# MC_Isolation_Schematic.net
KiCad netlist of a schematic drawn in Altium Designer
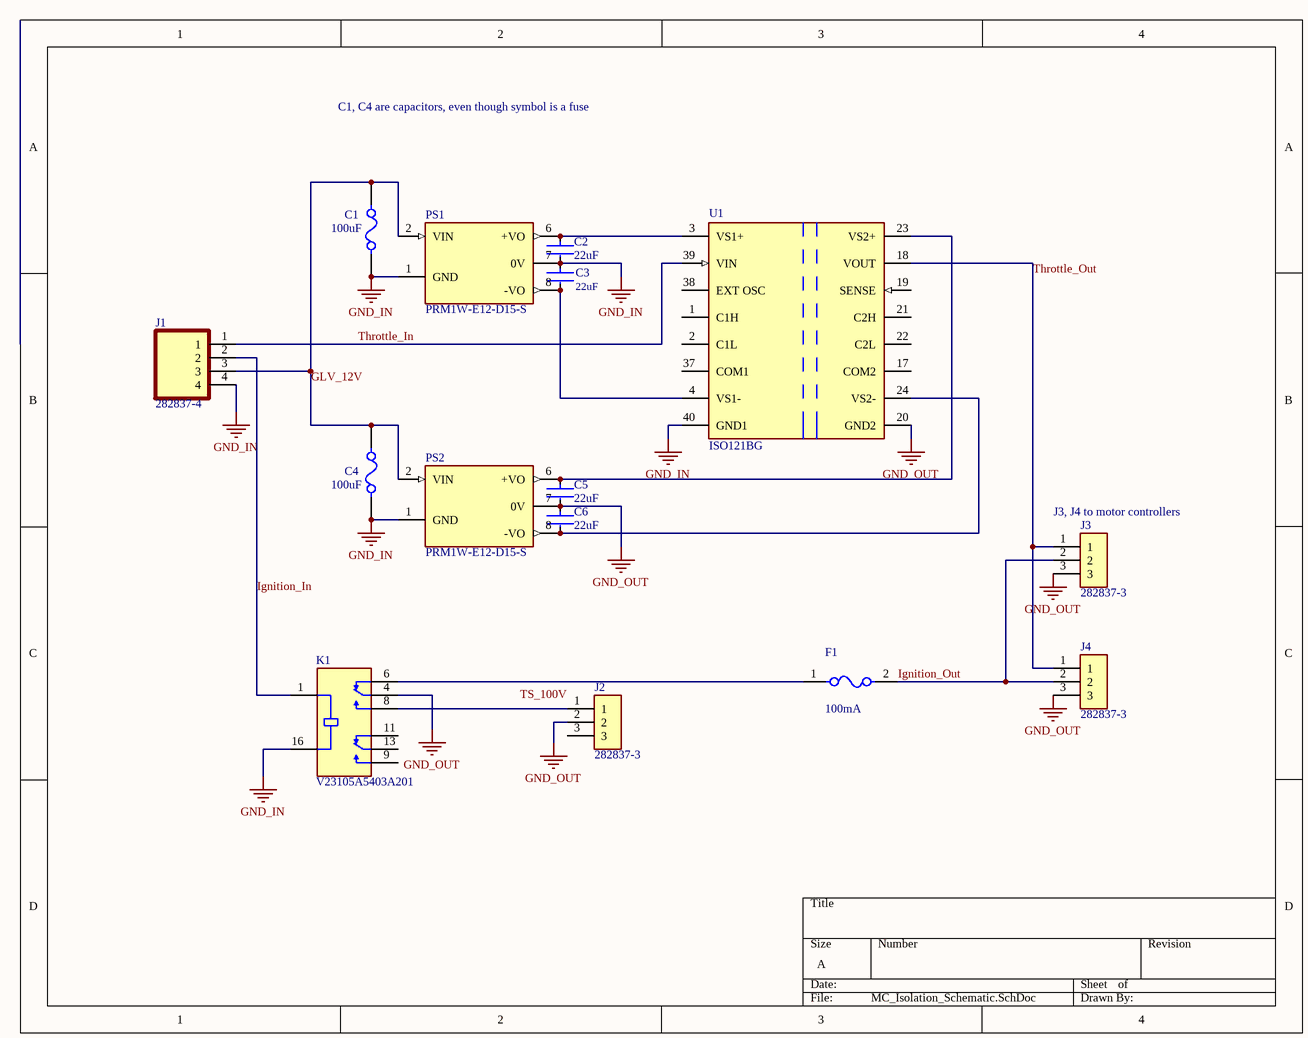
[diagram p0: MC_Isolation_Schematic.SchDoc]

(export (version "E")
  (design (tool "Eeschema 10.0.6"))
  (components
    (comp (ref "C1")
      (value "100uF")
      (footprint "FP-MF-R050-MFG")
      (description "PTC RESET FUSE 60V 500MA RADIAL")
      (fields
        (field (name "OCTOPART") "https://octopart.com/mf-r050-bourns-19418")
        (field (name "MANUFACTURER PART NUMBER") "MF-R050")
      )
      (libsource (lib "Altium Content Vault") (part "5bcf9b9f640e542cf0359d10258e979"))
    )
    (comp (ref "C2")
      (value "22uF")
      (footprint "FP-C3216-160-0_2-IPC_B")
      (description "Multilayer Ceramic Capacitors 1uF ±10% 50V X7R SMD 1206")
      (fields (field (name "VOLTAGE") "25V") (field (name "TOLERANCE") "10%"))
      (libsource (lib "Altium Content Vault") (part "11868f565c42a9108669ba33697ecf6"))
    )
    (comp (ref "C3")
      (value "22uF")
      (footprint "FP-C3216-160-0_2-IPC_B")
      (description "Multilayer Ceramic Capacitors 1uF ±10% 50V X7R SMD 1206")
      (fields (field (name "VOLTAGE") "25V") (field (name "TOLERANCE") "10%"))
      (libsource (lib "Altium Content Vault") (part "11868f565c42a9108669ba33697ecf6"))
    )
    (comp (ref "C4")
      (value "100uF")
      (footprint "FP-MF-R050-MFG")
      (description "PTC RESET FUSE 60V 500MA RADIAL")
      (fields
        (field (name "OCTOPART") "https://octopart.com/mf-r050-bourns-19418")
        (field (name "MANUFACTURER PART NUMBER") "MF-R050")
      )
      (libsource (lib "Altium Content Vault") (part "5bcf9b9f640e542cf0359d10258e979"))
    )
    (comp (ref "C5")
      (value "22uF")
      (footprint "FP-C3216-160-0_2-IPC_B")
      (description "Multilayer Ceramic Capacitors 1uF ±10% 50V X7R SMD 1206")
      (fields (field (name "VOLTAGE") "25V") (field (name "TOLERANCE") "10%"))
      (libsource (lib "Altium Content Vault") (part "11868f565c42a9108669ba33697ecf6"))
    )
    (comp (ref "C6")
      (value "22uF")
      (footprint "FP-C3216-160-0_2-IPC_B")
      (description "Multilayer Ceramic Capacitors 1uF ±10% 50V X7R SMD 1206")
      (fields (field (name "VOLTAGE") "25V") (field (name "TOLERANCE") "10%"))
      (libsource (lib "Altium Content Vault") (part "11868f565c42a9108669ba33697ecf6"))
    )
    (comp (ref "F1")
      (value "100mA")
      (footprint "FP-0154-MFG")
      (description "FUSE BOARD MNT 100MA 125VAC/VDC")
      (fields
        (field (name "OCTOPART") "https://octopart.com/0154.100dr-littelfuse-557956")
        (field (name "MANUFACTURER") "Littelfuse Inc")
      )
      (libsource (lib "") (part "5bcf9b9f640e542cf0359d10258e979_1"))
    )
    (comp (ref "J1")
      (value "282837-4")
      (footprint "TE_282837-4")
      (description "4 Position Wire to Board Terminal Block Horizontal with Board 0.200 (5.08mm)")
      (fields (field (name "MF") "TE Connectivity"))
      (libsource (lib "282837-4") (part "282837-4"))
    )
    (comp (ref "J2")
      (value "282837-3")
      (footprint "TE_282837-3")
      (description "Wire to Board 3 Position 5.08 mm Pitch 30-16 AWG Euro Style Terminal Block")
      (fields (field (name "MF") "TE Connectivity"))
      (libsource (lib "282837-3") (part "282837-3"))
    )
    (comp (ref "J3")
      (value "282837-3")
      (footprint "TE_282837-3")
      (description "Wire to Board 3 Position 5.08 mm Pitch 30-16 AWG Euro Style Terminal Block")
      (fields (field (name "MF") "TE Connectivity"))
      (libsource (lib "282837-3") (part "282837-3"))
    )
    (comp (ref "J4")
      (value "282837-3")
      (footprint "TE_282837-3")
      (description "Wire to Board 3 Position 5.08 mm Pitch 30-16 AWG Euro Style Terminal Block")
      (fields (field (name "MF") "TE Connectivity"))
      (libsource (lib "282837-3") (part "282837-3"))
    )
    (comp (ref "K1")
      (value "V23105A5403A201")
      (footprint "RELAY_1393793-8")
      (libsource (lib "V23105A5403A201") (part "V23105A5403A201"))
    )
    (comp (ref "PS1")
      (value "PRM1W-E12-D15-S")
      (footprint "CONV_PRM1W-E12-D15-S")
      (description "1 W, 8:1 Input Range, Single/Dual Regulated Output, 8 Pin SIP, 3000 Vdc Isolation, Dc-Dc Converter")
      (fields (field (name "MF") "{'manufacturer': u'CUI'}"))
      (libsource (lib "PRM1W-E12-D15-S") (part "PRM1W-E12-D15-S"))
    )
    (comp (ref "PS2")
      (value "PRM1W-E12-D15-S")
      (footprint "CONV_PRM1W-E12-D15-S")
      (description "1 W, 8:1 Input Range, Single/Dual Regulated Output, 8 Pin SIP, 3000 Vdc Isolation, Dc-Dc Converter")
      (fields (field (name "MF") "{'manufacturer': u'CUI'}"))
      (libsource (lib "PRM1W-E12-D15-S") (part "PRM1W-E12-D15-S"))
    )
    (comp (ref "U1")
      (value "ISO121BG")
      (footprint "FP-JVD0016A-MFG")
      (description "IC OPAMP ISOLATION 1 CIRC 16CDIP")
      (libsource (lib "Altium Content Vault") (part "aa3543eb15e901695e3e813befe1bad"))
    )
  )
  (nets
    (net (code "1") (name "/GLV_12V") (class "Default")
      (node (ref "C1") (pin "2") (pinfunction "2_2") (pintype "passive"))
      (node (ref "C4") (pin "2") (pinfunction "2_2") (pintype "passive"))
      (node (ref "J1") (pin "3") (pinfunction "3_3") (pintype "passive"))
      (node (ref "PS1") (pin "2") (pinfunction "VIN_2") (pintype "input"))
      (node (ref "PS2") (pin "2") (pinfunction "VIN_2") (pintype "input"))
    )
    (net (code "2") (name "/Ignition_In") (class "Default")
      (node (ref "J1") (pin "2") (pinfunction "2_2") (pintype "passive"))
      (node (ref "K1") (pin "1") (pinfunction "COIL1_1") (pintype "passive"))
    )
    (net (code "3") (name "/Ignition_Out") (class "Default")
      (node (ref "F1") (pin "2") (pinfunction "2_2") (pintype "passive"))
      (node (ref "J3") (pin "2") (pinfunction "2_2") (pintype "passive"))
      (node (ref "J4") (pin "2") (pinfunction "2_2") (pintype "passive"))
    )
    (net (code "5") (name "/Throttle_In") (class "Default")
      (node (ref "J1") (pin "1") (pinfunction "1_1") (pintype "passive"))
      (node (ref "U1") (pin "39") (pinfunction "VIN_39") (pintype "input"))
    )
    (net (code "6") (name "/Throttle_Out") (class "Default")
      (node (ref "J3") (pin "1") (pinfunction "1_1") (pintype "passive"))
      (node (ref "J4") (pin "1") (pinfunction "1_1") (pintype "passive"))
      (node (ref "U1") (pin "18") (pinfunction "VOUT_18") (pintype "power_in"))
    )
    (net (code "7") (name "GND_IN") (class "Default")
      (node (ref "C1") (pin "1") (pinfunction "1_1") (pintype "passive"))
      (node (ref "C2") (pin "2") (pinfunction "2_2") (pintype "passive"))
      (node (ref "C3") (pin "1") (pinfunction "1_1") (pintype "passive"))
      (node (ref "C4") (pin "1") (pinfunction "1_1") (pintype "passive"))
      (node (ref "J1") (pin "4") (pinfunction "4_4") (pintype "passive"))
      (node (ref "K1") (pin "16") (pinfunction "COIL2_16") (pintype "passive"))
      (node (ref "PS1") (pin "1") (pinfunction "GND_1") (pintype "power_in"))
      (node (ref "PS1") (pin "7") (pinfunction "0V_7") (pintype "passive"))
      (node (ref "PS2") (pin "1") (pinfunction "GND_1") (pintype "power_in"))
      (node (ref "U1") (pin "40") (pinfunction "GND1_40") (pintype "power_in"))
    )
    (net (code "8") (name "GND_OUT") (class "Default")
      (node (ref "C5") (pin "2") (pinfunction "2_2") (pintype "passive"))
      (node (ref "C6") (pin "1") (pinfunction "1_1") (pintype "passive"))
      (node (ref "J2") (pin "2") (pinfunction "2_2") (pintype "passive"))
      (node (ref "J3") (pin "3") (pinfunction "3_3") (pintype "passive"))
      (node (ref "J4") (pin "3") (pinfunction "3_3") (pintype "passive"))
      (node (ref "K1") (pin "4") (pinfunction "COM1_4") (pintype "passive"))
      (node (ref "PS2") (pin "7") (pinfunction "0V_7") (pintype "passive"))
      (node (ref "U1") (pin "20") (pinfunction "GND2_20") (pintype "power_in"))
    )
    (net (code "9") (name "Net-(K1-NC1)") (class "Default")
      (node (ref "F1") (pin "1") (pinfunction "1_1") (pintype "passive"))
      (node (ref "K1") (pin "6") (pinfunction "NC1_6") (pintype "passive"))
    )
    (net (code "10") (name "Net-(K1-NO1)") (class "Default")
      (node (ref "J2") (pin "1") (pinfunction "1_1") (pintype "passive"))
      (node (ref "K1") (pin "8") (pinfunction "NO1_8") (pintype "passive"))
    )
    (net (code "11") (name "Net-(PS1-+VO)") (class "Default")
      (node (ref "C2") (pin "1") (pinfunction "1_1") (pintype "passive"))
      (node (ref "PS1") (pin "6") (pinfunction "+VO_6") (pintype "output"))
      (node (ref "U1") (pin "3") (pinfunction "VS1+_3") (pintype "power_in"))
    )
    (net (code "12") (name "Net-(PS1--VO)") (class "Default")
      (node (ref "C3") (pin "2") (pinfunction "2_2") (pintype "passive"))
      (node (ref "PS1") (pin "8") (pinfunction "-VO_8") (pintype "output"))
      (node (ref "U1") (pin "4") (pinfunction "VS1-_4") (pintype "power_in"))
    )
    (net (code "13") (name "Net-(PS2-+VO)") (class "Default")
      (node (ref "C5") (pin "1") (pinfunction "1_1") (pintype "passive"))
      (node (ref "PS2") (pin "6") (pinfunction "+VO_6") (pintype "output"))
      (node (ref "U1") (pin "23") (pinfunction "VS2+_23") (pintype "power_in"))
    )
    (net (code "14") (name "Net-(PS2--VO)") (class "Default")
      (node (ref "C6") (pin "2") (pinfunction "2_2") (pintype "passive"))
      (node (ref "PS2") (pin "8") (pinfunction "-VO_8") (pintype "output"))
      (node (ref "U1") (pin "24") (pinfunction "VS2-_24") (pintype "power_in"))
    )
    (net (code "15") (name "unconnected-(J2-Pad3)") (class "Default")
      (node (ref "J2") (pin "3") (pinfunction "3_3") (pintype "passive"))
    )
    (net (code "16") (name "unconnected-(K1-COM2-Pad13)") (class "Default")
      (node (ref "K1") (pin "13") (pinfunction "COM2_13") (pintype "passive"))
    )
    (net (code "17") (name "unconnected-(K1-NC2-Pad11)") (class "Default")
      (node (ref "K1") (pin "11") (pinfunction "NC2_11") (pintype "passive"))
    )
    (net (code "18") (name "unconnected-(K1-NO2-Pad9)") (class "Default")
      (node (ref "K1") (pin "9") (pinfunction "NO2_9") (pintype "passive"))
    )
    (net (code "19") (name "unconnected-(U1-C1H-Pad1)") (class "Default")
      (node (ref "U1") (pin "1") (pinfunction "C1H_1") (pintype "passive"))
    )
    (net (code "20") (name "unconnected-(U1-C1L-Pad2)") (class "Default")
      (node (ref "U1") (pin "2") (pinfunction "C1L_2") (pintype "passive"))
    )
    (net (code "21") (name "unconnected-(U1-C2H-Pad21)") (class "Default")
      (node (ref "U1") (pin "21") (pinfunction "C2H_21") (pintype "passive"))
    )
    (net (code "22") (name "unconnected-(U1-C2L-Pad22)") (class "Default")
      (node (ref "U1") (pin "22") (pinfunction "C2L_22") (pintype "passive"))
    )
    (net (code "23") (name "unconnected-(U1-COM1-Pad37)") (class "Default")
      (node (ref "U1") (pin "37") (pinfunction "COM1_37") (pintype "passive"))
    )
    (net (code "24") (name "unconnected-(U1-COM2-Pad17)") (class "Default")
      (node (ref "U1") (pin "17") (pinfunction "COM2_17") (pintype "passive"))
    )
    (net (code "25") (name "unconnected-(U1-EXT_OSC-Pad38)") (class "Default")
      (node (ref "U1") (pin "38") (pinfunction "EXT_OSC_38") (pintype "passive"))
    )
    (net (code "26") (name "unconnected-(U1-SENSE-Pad19)") (class "Default")
      (node (ref "U1") (pin "19") (pinfunction "SENSE_19") (pintype "input"))
    )
  )
)
